# Sheet3.net
KiCad netlist of a schematic drawn in Altium Designer
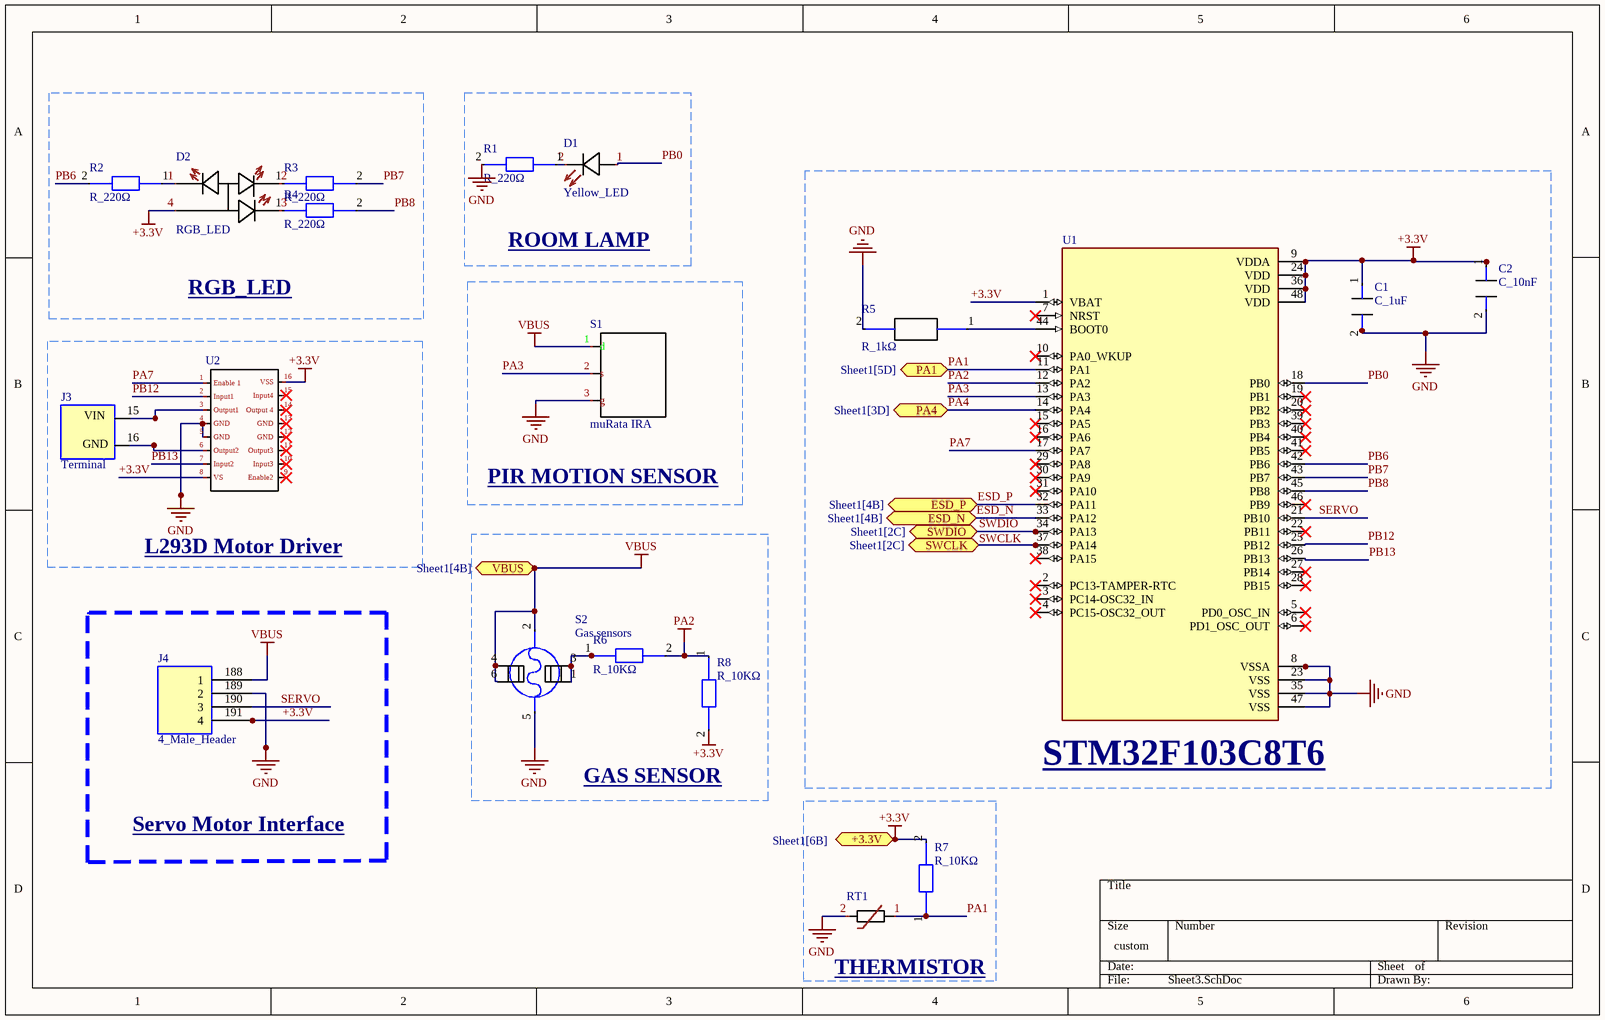
[diagram p0: Sheet3.SchDoc]

(export (version "E")
  (design (tool "Eeschema 10.0.6"))
  (components
    (comp (ref "C1")
      (value "C_1uF")
      (footprint "CAP_1uF")
      (description "CAP CER 1uF 50V X7R 0805")
      (fields (field (name "MFR") "Samsung Electro-Mechanics") (field (name "MFR PART #") "CL21B105KBFNNNE"))
      (libsource (lib "Schlib3") (part "C_1uF"))
    )
    (comp (ref "C2")
      (value "C_10nF")
      (footprint "CAP_10nF")
      (description "CAP CER 10nF 50V X7R 0805")
      (fields (field (name "MFR") "Samsung Electro-Mechanics") (field (name "MFR PART#") "CL21B103KBANNNC"))
      (libsource (lib "Schlib3") (part "C_10nF"))
    )
    (comp (ref "D1")
      (value "Yellow_LED")
      (footprint "LED_YELLOW")
      (description "LED YELLOW GREEN 0805 SMD")
      (libsource (lib "Schlib3") (part "Yellow_LED"))
    )
    (comp (ref "D2")
      (value "RGB_LED")
      (footprint "RGB_LED")
      (description "120° SMD-4P,2x1.2mm LED Indication - Discrete")
      (fields (field (name "MF") "MEIHUA") (field (name "MPN") "MHT170RGBCT"))
      (libsource (lib "Schlib3") (part "RGB_LED"))
    )
    (comp (ref "J3")
      (value "Terminal")
      (footprint "Terminal Block")
      (description "0.05~1.3 -40℃~+110℃ 13.5A 1x2P Green 16~30 Through Hole 2 1 5.08mm Through Hole Wire to Board RoHS")
      (fields (field (name "MFR") "TE Connectivity") (field (name "MFR PART #") "282837-2"))
      (libsource (lib "Schlib3") (part "Terminal"))
    )
    (comp (ref "J4")
      (value "4_Male_Header")
      (footprint "4_MALE_HEADER")
      (fields (field (name "MFR") "TE Connectivity") (field (name "MFR PART #") "3-641215-4"))
      (libsource (lib "Schlib3") (part "4_Male_Header"))
    )
    (comp (ref "R1")
      (value "R_220Ω")
      (footprint "RES_220")
      (description "RES 220Ω ±1% 125mW 0805")
      (fields (field (name "MFR") "UNI-ROYAL") (field (name "MFR PART #") "0805W8F2200T5E"))
      (libsource (lib "Schlib3") (part "R_220Ω"))
    )
    (comp (ref "R2")
      (value "R_220Ω")
      (footprint "RES_220")
      (description "RES 220Ω ±1% 125mW 0805")
      (fields (field (name "MFR") "UNI-ROYAL") (field (name "MFR PART #") "0805W8F2200T5E"))
      (libsource (lib "Schlib3") (part "R_220Ω"))
    )
    (comp (ref "R3")
      (value "R_220Ω")
      (footprint "RES_220")
      (description "RES 220Ω ±1% 125mW 0805")
      (fields (field (name "MFR") "UNI-ROYAL") (field (name "MFR PART #") "0805W8F2200T5E"))
      (libsource (lib "Schlib3") (part "R_220Ω"))
    )
    (comp (ref "R4")
      (value "R_220Ω")
      (footprint "RES_220")
      (description "RES 220Ω ±1% 125mW 0805")
      (fields (field (name "MFR") "UNI-ROYAL") (field (name "MFR PART #") "0805W8F2200T5E"))
      (libsource (lib "Schlib3") (part "R_220Ω"))
    )
    (comp (ref "R5")
      (value "R_1kΩ")
      (footprint "RES_1K")
      (description "RES 1kΩ ±1% 100mW 0805")
      (fields (field (name "MFU PART #") "FRC0603F1001TS"))
      (libsource (lib "Schlib3") (part "R_1kΩ"))
    )
    (comp (ref "R6")
      (value "R_10KΩ")
      (footprint "RES_10K")
      (description "RES 10kΩ ±1% 125mW 0805")
      (fields (field (name "MFR") "FOJAN") (field (name "MFR PART #") "FRC0805F1002TS"))
      (libsource (lib "Schlib3") (part "R_10KΩ"))
    )
    (comp (ref "R7")
      (value "R_10KΩ")
      (footprint "RES_10K")
      (description "RES 10kΩ ±1% 125mW 0805")
      (fields (field (name "MFR") "FOJAN") (field (name "MFR PART #") "FRC0805F1002TS"))
      (libsource (lib "Schlib3") (part "R_10KΩ"))
    )
    (comp (ref "R8")
      (value "R_10KΩ")
      (footprint "RES_10K")
      (description "RES 10kΩ ±1% 125mW 0805")
      (fields (field (name "MFR") "FOJAN") (field (name "MFR PART #") "FRC0805F1002TS"))
      (libsource (lib "Schlib3") (part "R_10KΩ"))
    )
    (comp (ref "RT1")
      (value "THERMISTOR")
      (footprint "NTC_THERMISTOR")
      (description "THERMISTOR NTC 10kΩ 3950K 0805")
      (fields (field (name "MF") "KUU"))
      (libsource (lib "Schlib3") (part "THERMISTOR"))
    )
    (comp (ref "S1")
      (value "muRata IRA")
      (footprint "OPTICAL_SENSOR")
      (description "Through Hole Optical Motion Sensors RoHS")
      (fields (field (name "MF") "muRata") (field (name "MPN") "IRA-S210ST01"))
      (libsource (lib "Schlib3") (part "muRata IRA"))
    )
    (comp (ref "S2")
      (value "Gas sensors")
      (footprint "GAS_SENSOR")
      (description "300ppm~10000ppm Through Hole Gas Sensors")
      (fields (field (name "MF") "Zhengzhou Winsen Elec Tech") (field (name "MPN") "MQ-5"))
      (libsource (lib "Schlib3") (part "Gas sensors"))
    )
    (comp (ref "U1")
      (value "STM32F103C8T6")
      (footprint "STM32")
      (fields (field (name "MF") "STMicroelectronics"))
      (libsource (lib "Schlib3") (part "STM32F103C8T6"))
    )
    (comp (ref "U2")
      (value "L293D Motor Driver")
      (footprint "L293D")
      (description "PUSH-PULL FOUR CHANNEL DRIVER WITH DIODES")
      (fields (field (name "MFR") "HGSEMI") (field (name "MRF PART #") "L293DDM/TR"))
      (libsource (lib "Schlib3") (part "L293D Motor Driver"))
    )
  )
  (nets
    (net (code "1") (name "+3.3V") (class "Default")
      (node (ref "C1") (pin "1") (pinfunction "1_1") (pintype "passive"))
      (node (ref "C2") (pin "1") (pinfunction "1_1") (pintype "passive"))
      (node (ref "D2") (pin "4") (pinfunction "4_4") (pintype "passive"))
      (node (ref "J4") (pin "191") (pinfunction "4_191") (pintype "passive"))
      (node (ref "R7") (pin "2") (pinfunction "15_2") (pintype "passive"))
      (node (ref "R8") (pin "2") (pinfunction "15_2") (pintype "passive"))
      (node (ref "U1") (pin "1") (pinfunction "VBAT_1") (pintype "bidirectional"))
      (node (ref "U1") (pin "24") (pinfunction "VDD_24") (pintype "power_in"))
      (node (ref "U1") (pin "36") (pinfunction "VDD_36") (pintype "power_in"))
      (node (ref "U1") (pin "48") (pinfunction "VDD_48") (pintype "power_in"))
      (node (ref "U1") (pin "9") (pinfunction "VDDA_9") (pintype "power_in"))
      (node (ref "U2") (pin "16") (pinfunction "VSS_16") (pintype "passive"))
      (node (ref "U2") (pin "8") (pinfunction "VS_8") (pintype "passive"))
    )
    (net (code "2") (name "/ESD_N") (class "Default")
      (node (ref "U1") (pin "33") (pinfunction "PA12_33") (pintype "bidirectional"))
    )
    (net (code "3") (name "/ESD_P") (class "Default")
      (node (ref "U1") (pin "32") (pinfunction "PA11_32") (pintype "bidirectional"))
    )
    (net (code "4") (name "/PA1") (class "Default")
      (node (ref "R7") (pin "1") (pinfunction "14_1") (pintype "passive"))
      (node (ref "RT1") (pin "1") (pinfunction "1_1") (pintype "passive"))
      (node (ref "U1") (pin "11") (pinfunction "PA1_11") (pintype "bidirectional"))
    )
    (net (code "5") (name "/PA3") (class "Default")
      (node (ref "S1") (pin "2") (pinfunction "s_2") (pintype "passive"))
      (node (ref "U1") (pin "13") (pinfunction "PA3_13") (pintype "bidirectional"))
    )
    (net (code "6") (name "/PA4") (class "Default")
      (node (ref "U1") (pin "14") (pinfunction "PA4_14") (pintype "bidirectional"))
    )
    (net (code "7") (name "/PA7") (class "Default")
      (node (ref "U1") (pin "17") (pinfunction "PA7_17") (pintype "bidirectional"))
      (node (ref "U2") (pin "1") (pinfunction "Enable_1_1") (pintype "passive"))
    )
    (net (code "8") (name "/PB0") (class "Default")
      (node (ref "D1") (pin "1") (pinfunction "13_1") (pintype "passive"))
      (node (ref "U1") (pin "18") (pinfunction "PB0_18") (pintype "bidirectional"))
    )
    (net (code "9") (name "/PB6") (class "Default")
      (node (ref "R2") (pin "2") (pinfunction "15_2") (pintype "passive"))
      (node (ref "U1") (pin "42") (pinfunction "PB6_42") (pintype "bidirectional"))
    )
    (net (code "10") (name "/PB7") (class "Default")
      (node (ref "R3") (pin "2") (pinfunction "15_2") (pintype "passive"))
      (node (ref "U1") (pin "43") (pinfunction "PB7_43") (pintype "bidirectional"))
    )
    (net (code "11") (name "/PB8") (class "Default")
      (node (ref "R4") (pin "2") (pinfunction "15_2") (pintype "passive"))
      (node (ref "U1") (pin "45") (pinfunction "PB8_45") (pintype "bidirectional"))
    )
    (net (code "12") (name "/PB12") (class "Default")
      (node (ref "U1") (pin "25") (pinfunction "PB12_25") (pintype "bidirectional"))
      (node (ref "U2") (pin "2") (pinfunction "Input1_2") (pintype "passive"))
    )
    (net (code "13") (name "/PB13") (class "Default")
      (node (ref "U1") (pin "26") (pinfunction "PB13_26") (pintype "bidirectional"))
      (node (ref "U2") (pin "7") (pinfunction "Input2_7") (pintype "passive"))
    )
    (net (code "14") (name "/SERVO") (class "Default")
      (node (ref "J4") (pin "190") (pinfunction "3_190") (pintype "passive"))
      (node (ref "U1") (pin "21") (pinfunction "PB10_21") (pintype "bidirectional"))
    )
    (net (code "15") (name "/SWCLK") (class "Default")
      (node (ref "U1") (pin "37") (pinfunction "PA14_37") (pintype "bidirectional"))
    )
    (net (code "16") (name "/SWDIO") (class "Default")
      (node (ref "U1") (pin "34") (pinfunction "PA13_34") (pintype "bidirectional"))
    )
    (net (code "17") (name "GND") (class "Default")
      (node (ref "C1") (pin "2") (pinfunction "2_2") (pintype "passive"))
      (node (ref "C2") (pin "2") (pinfunction "2_2") (pintype "passive"))
      (node (ref "J4") (pin "189") (pinfunction "2_189") (pintype "passive"))
      (node (ref "R1") (pin "2") (pinfunction "15_2") (pintype "passive"))
      (node (ref "R5") (pin "2") (pinfunction "15_2") (pintype "passive"))
      (node (ref "RT1") (pin "2") (pinfunction "2_2") (pintype "passive"))
      (node (ref "S1") (pin "3") (pinfunction "g_3") (pintype "passive"))
      (node (ref "S2") (pin "5") (pinfunction "5_5") (pintype "passive"))
      (node (ref "U1") (pin "23") (pinfunction "VSS_23") (pintype "power_in"))
      (node (ref "U1") (pin "35") (pinfunction "VSS_35") (pintype "power_in"))
      (node (ref "U1") (pin "47") (pinfunction "VSS_47") (pintype "power_in"))
      (node (ref "U1") (pin "8") (pinfunction "VSSA_8") (pintype "power_in"))
      (node (ref "U2") (pin "4") (pinfunction "GND_4") (pintype "passive"))
      (node (ref "U2") (pin "5") (pinfunction "GND_5") (pintype "passive"))
    )
    (net (code "18") (name "Net-(D2-13)") (class "Default")
      (node (ref "D2") (pin "1") (pinfunction "13_1") (pintype "passive"))
      (node (ref "R2") (pin "1") (pinfunction "14_1") (pintype "passive"))
    )
    (net (code "19") (name "Net-(R1-14)") (class "Default")
      (node (ref "D1") (pin "2") (pinfunction "2_2") (pintype "passive"))
      (node (ref "R1") (pin "1") (pinfunction "14_1") (pintype "passive"))
    )
    (net (code "20") (name "Net-(R3-14)") (class "Default")
      (node (ref "D2") (pin "2") (pinfunction "2_2") (pintype "passive"))
      (node (ref "R3") (pin "1") (pinfunction "14_1") (pintype "passive"))
    )
    (net (code "21") (name "Net-(R4-14)") (class "Default")
      (node (ref "D2") (pin "3") (pinfunction "3_3") (pintype "passive"))
      (node (ref "R4") (pin "1") (pinfunction "14_1") (pintype "passive"))
    )
    (net (code "22") (name "Net-(R5-14)") (class "Default")
      (node (ref "R5") (pin "1") (pinfunction "14_1") (pintype "passive"))
      (node (ref "U1") (pin "44") (pinfunction "BOOT0_44") (pintype "input"))
    )
    (net (code "23") (name "Net-(R6-14)") (class "Default")
      (node (ref "R6") (pin "1") (pinfunction "14_1") (pintype "passive"))
      (node (ref "S2") (pin "1") (pinfunction "1_1") (pintype "passive"))
      (node (ref "S2") (pin "3") (pinfunction "3_3") (pintype "passive"))
    )
    (net (code "24") (name "Net-(U2-Output1)") (class "Default")
      (node (ref "J3") (pin "15") (pinfunction "15_15") (pintype "passive"))
      (node (ref "U2") (pin "3") (pinfunction "Output1_3") (pintype "passive"))
    )
    (net (code "25") (name "Net-(U2-Output2)") (class "Default")
      (node (ref "J3") (pin "16") (pinfunction "16_16") (pintype "passive"))
      (node (ref "U2") (pin "6") (pinfunction "Output2_6") (pintype "passive"))
    )
    (net (code "26") (name "PA2") (class "Default")
      (node (ref "R6") (pin "2") (pinfunction "15_2") (pintype "passive"))
      (node (ref "R8") (pin "1") (pinfunction "14_1") (pintype "passive"))
      (node (ref "U1") (pin "12") (pinfunction "PA2_12") (pintype "bidirectional"))
    )
    (net (code "27") (name "VBUS") (class "Default")
      (node (ref "J4") (pin "188") (pinfunction "1_188") (pintype "passive"))
      (node (ref "S1") (pin "1") (pinfunction "d_1") (pintype "passive"))
      (node (ref "S2") (pin "2") (pinfunction "2_2") (pintype "passive"))
      (node (ref "S2") (pin "4") (pinfunction "4_4") (pintype "passive"))
      (node (ref "S2") (pin "6") (pinfunction "6_6") (pintype "passive"))
    )
    (net (code "28") (name "unconnected-(U1-NRST-Pad7)") (class "Default")
      (node (ref "U1") (pin "7") (pinfunction "NRST_7") (pintype "input+no_connect"))
    )
    (net (code "29") (name "unconnected-(U1-PA0_WKUP-Pad10)") (class "Default")
      (node (ref "U1") (pin "10") (pinfunction "PA0_WKUP_10") (pintype "bidirectional+no_connect"))
    )
    (net (code "30") (name "unconnected-(U1-PA5-Pad15)") (class "Default")
      (node (ref "U1") (pin "15") (pinfunction "PA5_15") (pintype "bidirectional+no_connect"))
    )
    (net (code "31") (name "unconnected-(U1-PA6-Pad16)") (class "Default")
      (node (ref "U1") (pin "16") (pinfunction "PA6_16") (pintype "bidirectional+no_connect"))
    )
    (net (code "32") (name "unconnected-(U1-PA8-Pad29)") (class "Default")
      (node (ref "U1") (pin "29") (pinfunction "PA8_29") (pintype "bidirectional+no_connect"))
    )
    (net (code "33") (name "unconnected-(U1-PA9-Pad30)") (class "Default")
      (node (ref "U1") (pin "30") (pinfunction "PA9_30") (pintype "bidirectional+no_connect"))
    )
    (net (code "34") (name "unconnected-(U1-PA10-Pad31)") (class "Default")
      (node (ref "U1") (pin "31") (pinfunction "PA10_31") (pintype "bidirectional+no_connect"))
    )
    (net (code "35") (name "unconnected-(U1-PA15-Pad38)") (class "Default")
      (node (ref "U1") (pin "38") (pinfunction "PA15_38") (pintype "bidirectional+no_connect"))
    )
    (net (code "36") (name "unconnected-(U1-PB1-Pad19)") (class "Default")
      (node (ref "U1") (pin "19") (pinfunction "PB1_19") (pintype "bidirectional+no_connect"))
    )
    (net (code "37") (name "unconnected-(U1-PB2-Pad20)") (class "Default")
      (node (ref "U1") (pin "20") (pinfunction "PB2_20") (pintype "bidirectional+no_connect"))
    )
    (net (code "38") (name "unconnected-(U1-PB3-Pad39)") (class "Default")
      (node (ref "U1") (pin "39") (pinfunction "PB3_39") (pintype "bidirectional+no_connect"))
    )
    (net (code "39") (name "unconnected-(U1-PB4-Pad40)") (class "Default")
      (node (ref "U1") (pin "40") (pinfunction "PB4_40") (pintype "bidirectional+no_connect"))
    )
    (net (code "40") (name "unconnected-(U1-PB5-Pad41)") (class "Default")
      (node (ref "U1") (pin "41") (pinfunction "PB5_41") (pintype "bidirectional+no_connect"))
    )
    (net (code "41") (name "unconnected-(U1-PB9-Pad46)") (class "Default")
      (node (ref "U1") (pin "46") (pinfunction "PB9_46") (pintype "bidirectional+no_connect"))
    )
    (net (code "42") (name "unconnected-(U1-PB11-Pad22)") (class "Default")
      (node (ref "U1") (pin "22") (pinfunction "PB11_22") (pintype "bidirectional+no_connect"))
    )
    (net (code "43") (name "unconnected-(U1-PB14-Pad27)") (class "Default")
      (node (ref "U1") (pin "27") (pinfunction "PB14_27") (pintype "bidirectional+no_connect"))
    )
    (net (code "44") (name "unconnected-(U1-PB15-Pad28)") (class "Default")
      (node (ref "U1") (pin "28") (pinfunction "PB15_28") (pintype "bidirectional+no_connect"))
    )
    (net (code "45") (name "unconnected-(U1-PC13-TAMPER-RTC-Pad2)") (class "Default")
      (node (ref "U1") (pin "2") (pinfunction "PC13-TAMPER-RTC_2") (pintype "bidirectional+no_connect"))
    )
    (net (code "46") (name "unconnected-(U1-PC14-OSC32_IN-Pad3)") (class "Default")
      (node (ref "U1") (pin "3") (pinfunction "PC14-OSC32_IN_3") (pintype "bidirectional+no_connect"))
    )
    (net (code "47") (name "unconnected-(U1-PC15-OSC32_OUT-Pad4)") (class "Default")
      (node (ref "U1") (pin "4") (pinfunction "PC15-OSC32_OUT_4") (pintype "bidirectional+no_connect"))
    )
    (net (code "48") (name "unconnected-(U1-PD0_OSC_IN-Pad5)") (class "Default")
      (node (ref "U1") (pin "5") (pinfunction "PD0_OSC_IN_5") (pintype "bidirectional+no_connect"))
    )
    (net (code "49") (name "unconnected-(U1-PD1_OSC_OUT-Pad6)") (class "Default")
      (node (ref "U1") (pin "6") (pinfunction "PD1_OSC_OUT_6") (pintype "bidirectional+no_connect"))
    )
    (net (code "50") (name "unconnected-(U2-Enable2-Pad9)") (class "Default")
      (node (ref "U2") (pin "9") (pinfunction "Enable2_9") (pintype "passive+no_connect"))
    )
    (net (code "51") (name "unconnected-(U2-GND-Pad12)") (class "Default")
      (node (ref "U2") (pin "12") (pinfunction "GND_12") (pintype "passive+no_connect"))
    )
    (net (code "52") (name "unconnected-(U2-GND-Pad13)") (class "Default")
      (node (ref "U2") (pin "13") (pinfunction "GND_13") (pintype "passive+no_connect"))
    )
    (net (code "53") (name "unconnected-(U2-Input3-Pad10)") (class "Default")
      (node (ref "U2") (pin "10") (pinfunction "Input3_10") (pintype "passive+no_connect"))
    )
    (net (code "54") (name "unconnected-(U2-Input4-Pad15)") (class "Default")
      (node (ref "U2") (pin "15") (pinfunction "Input4_15") (pintype "passive+no_connect"))
    )
    (net (code "55") (name "unconnected-(U2-Output3-Pad11)") (class "Default")
      (node (ref "U2") (pin "11") (pinfunction "Output3_11") (pintype "passive+no_connect"))
    )
    (net (code "56") (name "unconnected-(U2-Output_4-Pad14)") (class "Default")
      (node (ref "U2") (pin "14") (pinfunction "Output_4_14") (pintype "passive+no_connect"))
    )
  )
)
